# BandpassedGainAmpSMT.net
KiCad netlist of a schematic drawn in EAGLE
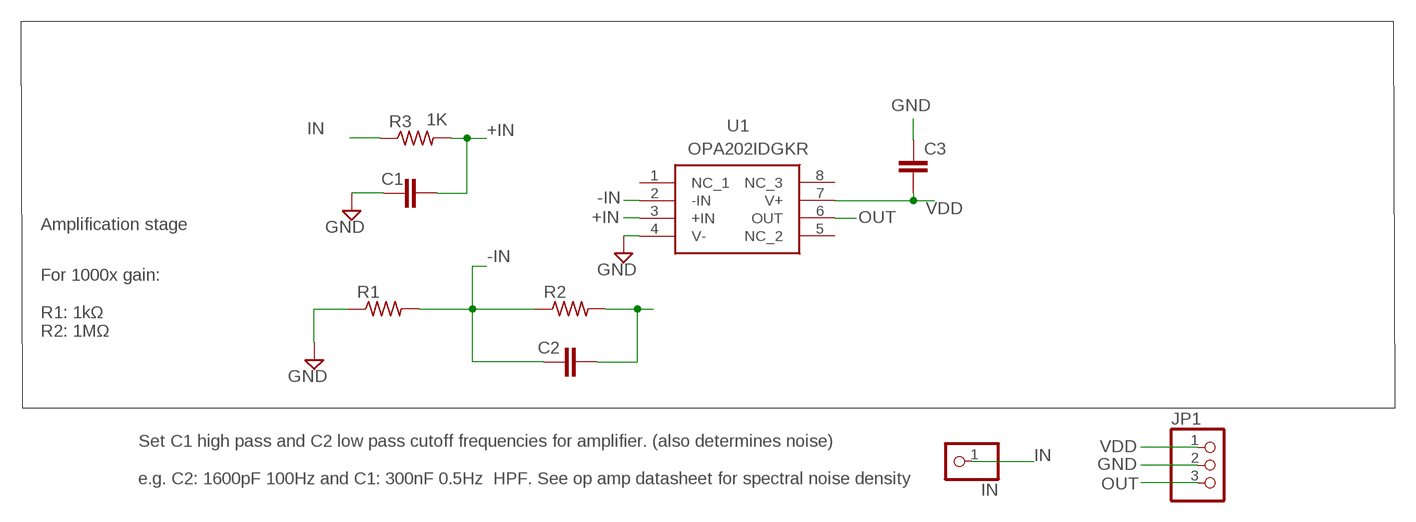
[diagram p0: schematic, sheet 1]

(export (version "E")
  (design (tool "Eeschema 10.0.6"))
  (components
    (comp (ref "C1")
      (value "C-EUC0402")
      (footprint "eagle-import:C0402")
      (libsource (lib "eagle-import") (part "C-EUC0402"))
    )
    (comp (ref "C2")
      (value "C-EUC0402")
      (footprint "eagle-import:C0402")
      (libsource (lib "eagle-import") (part "C-EUC0402"))
    )
    (comp (ref "C3")
      (value "C-EUC0402")
      (footprint "eagle-import:C0402")
      (libsource (lib "eagle-import") (part "C-EUC0402"))
    )
    (comp (ref "IN")
      (value "PINHD-1X1")
      (footprint "eagle-import:1X01")
      (libsource (lib "eagle-import") (part "PINHD-1X1"))
    )
    (comp (ref "JP1")
      (value "PINHD-1X3")
      (footprint "eagle-import:1X03")
      (libsource (lib "eagle-import") (part "PINHD-1X3"))
    )
    (comp (ref "R1")
      (value "R-US_R0402")
      (footprint "eagle-import:R0402")
      (libsource (lib "eagle-import") (part "R-US_R0402"))
    )
    (comp (ref "R2")
      (value "R-US_R0402")
      (footprint "eagle-import:R0402")
      (libsource (lib "eagle-import") (part "R-US_R0402"))
    )
    (comp (ref "R3")
      (value "1K")
      (footprint "eagle-import:R0402")
      (libsource (lib "eagle-import") (part "R-US_R0402"))
    )
    (comp (ref "U1")
      (value "OPA202IDGKR")
      (footprint "eagle-import:SOP65P490X110-8N")
      (fields (field (name "MOUSER_PART_NUMBER") "595-OPA202IDGKR"))
      (libsource (lib "eagle-import") (part "OPA202IDGKR"))
    )
  )
  (nets
    (net (code "1") (name "/+IN") (class "Default")
      (node (ref "C1") (pin "2") (pinfunction "2_2") (pintype "passive"))
      (node (ref "R3") (pin "2") (pinfunction "2_2") (pintype "passive"))
      (node (ref "U1") (pin "3") (pinfunction "+IN_3") (pintype "bidirectional"))
    )
    (net (code "2") (name "/-IN") (class "Default")
      (node (ref "C2") (pin "1") (pinfunction "1_1") (pintype "passive"))
      (node (ref "R1") (pin "2") (pinfunction "2_2") (pintype "passive"))
      (node (ref "R2") (pin "1") (pinfunction "1_1") (pintype "passive"))
      (node (ref "U1") (pin "2") (pinfunction "-IN_2") (pintype "bidirectional"))
    )
    (net (code "3") (name "/IN") (class "Default")
      (node (ref "IN") (pin "1") (pinfunction "1_1") (pintype "passive"))
      (node (ref "R3") (pin "1") (pinfunction "1_1") (pintype "passive"))
    )
    (net (code "4") (name "/OUT") (class "Default")
      (node (ref "JP1") (pin "3") (pinfunction "3_3") (pintype "passive"))
      (node (ref "U1") (pin "6") (pinfunction "OUT_6") (pintype "bidirectional"))
    )
    (net (code "5") (name "/VDD") (class "Default")
      (node (ref "C3") (pin "2") (pinfunction "2_2") (pintype "passive"))
      (node (ref "JP1") (pin "1") (pinfunction "1_1") (pintype "passive"))
      (node (ref "U1") (pin "7") (pinfunction "V+_7") (pintype "bidirectional"))
    )
    (net (code "6") (name "GND") (class "Default")
      (node (ref "C1") (pin "1") (pinfunction "1_1") (pintype "passive"))
      (node (ref "C3") (pin "1") (pinfunction "1_1") (pintype "passive"))
      (node (ref "JP1") (pin "2") (pinfunction "2_2") (pintype "passive"))
      (node (ref "R1") (pin "1") (pinfunction "1_1") (pintype "passive"))
      (node (ref "U1") (pin "4") (pinfunction "V-_4") (pintype "bidirectional"))
    )
    (net (code "7") (name "Net-(C2-Pad2)") (class "Default")
      (node (ref "C2") (pin "2") (pinfunction "2_2") (pintype "passive"))
      (node (ref "R2") (pin "2") (pinfunction "2_2") (pintype "passive"))
    )
    (net (code "8") (name "unconnected-(U1-NC_1-Pad1)") (class "Default")
      (node (ref "U1") (pin "1") (pinfunction "NC_1_1") (pintype "bidirectional"))
    )
    (net (code "9") (name "unconnected-(U1-NC_2-Pad5)") (class "Default")
      (node (ref "U1") (pin "5") (pinfunction "NC_2_5") (pintype "bidirectional"))
    )
    (net (code "10") (name "unconnected-(U1-NC_3-Pad8)") (class "Default")
      (node (ref "U1") (pin "8") (pinfunction "NC_3_8") (pintype "bidirectional"))
    )
  )
)
